# controle_motor_comunicacao.net
KiCad netlist of a schematic drawn in Altium Designer
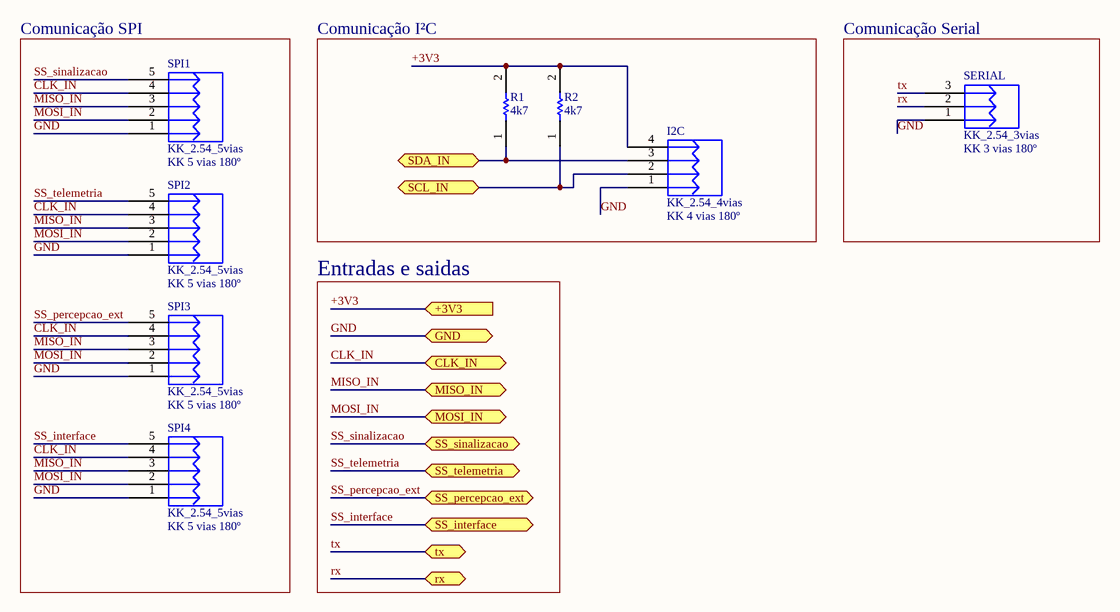
[diagram p0: controle_motor_comunicacao.SchDoc]

(export (version "E")
  (design (tool "Eeschema 10.0.6"))
  (components
    (comp (ref "I2C")
      (value "KK_2.54_4vias")
      (footprint "KK_4vias_180°")
      (description "Conector KK 2.54mm 4 vias")
      (fields (field (name "VALOR") "KK 4 vias 180º"))
      (libsource (lib "Conectores_Sch") (part "KK_2.54_4vias"))
    )
    (comp (ref "R1")
      (value "4k7")
      (footprint "RESC3216X60N")
      (description "RES 1206 5%")
      (fields
        (field (name "MANUFACTURER_PART_NUMBER") "CRCW12064K70FKEA")
        (field (name "MOUSER PART NUMBER") "71-CRCW1206-4.7K-E3")
      )
      (libsource (lib "RoboHospitalar") (part "RES 1206"))
    )
    (comp (ref "R2")
      (value "4k7")
      (footprint "RESC3216X60N")
      (description "RES 1206 5%")
      (fields
        (field (name "MANUFACTURER_PART_NUMBER") "CRCW12064K70FKEA")
        (field (name "MOUSER PART NUMBER") "71-CRCW1206-4.7K-E3")
      )
      (libsource (lib "RoboHospitalar") (part "RES 1206"))
    )
    (comp (ref "SERIAL")
      (value "KK_2.54_3vias")
      (footprint "KK_3vias_180º")
      (description "Conector KK 2.54mm 3 vias")
      (fields (field (name "VALOR") "KK 3 vias 180º"))
      (libsource (lib "Conectores_Sch") (part "KK_2.54_3vias"))
    )
    (comp (ref "SPI1")
      (value "KK_2.54_5vias")
      (footprint "KK_5vias_180°")
      (description "Conector KK 2.54mm 5 vias")
      (fields (field (name "VALOR") "KK 5 vias 180º"))
      (libsource (lib "Conectores_Sch") (part "KK_2.54_5vias"))
    )
    (comp (ref "SPI2")
      (value "KK_2.54_5vias")
      (footprint "KK_5vias_180°")
      (description "Conector KK 2.54mm 5 vias")
      (fields (field (name "VALOR") "KK 5 vias 180º"))
      (libsource (lib "Conectores_Sch") (part "KK_2.54_5vias"))
    )
    (comp (ref "SPI3")
      (value "KK_2.54_5vias")
      (footprint "KK_5vias_180°")
      (description "Conector KK 2.54mm 5 vias")
      (fields (field (name "VALOR") "KK 5 vias 180º"))
      (libsource (lib "Conectores_Sch") (part "KK_2.54_5vias"))
    )
    (comp (ref "SPI4")
      (value "KK_2.54_5vias")
      (footprint "KK_5vias_180°")
      (description "Conector KK 2.54mm 5 vias")
      (fields (field (name "VALOR") "KK 5 vias 180º"))
      (libsource (lib "Conectores_Sch") (part "KK_2.54_5vias"))
    )
  )
  (nets
    (net (code "1") (name "/+3V3") (class "Default")
      (node (ref "I2C") (pin "4") (pintype "passive"))
      (node (ref "R1") (pin "2") (pinfunction "2_2") (pintype "passive"))
      (node (ref "R2") (pin "2") (pinfunction "2_2") (pintype "passive"))
    )
    (net (code "2") (name "/CLK_IN") (class "Default")
      (node (ref "SPI1") (pin "4") (pintype "passive"))
      (node (ref "SPI2") (pin "4") (pintype "passive"))
      (node (ref "SPI3") (pin "4") (pintype "passive"))
      (node (ref "SPI4") (pin "4") (pintype "passive"))
    )
    (net (code "3") (name "/GND") (class "Default")
      (node (ref "I2C") (pin "1") (pintype "passive"))
      (node (ref "SERIAL") (pin "1") (pintype "passive"))
      (node (ref "SPI1") (pin "1") (pintype "passive"))
      (node (ref "SPI2") (pin "1") (pintype "passive"))
      (node (ref "SPI3") (pin "1") (pintype "passive"))
      (node (ref "SPI4") (pin "1") (pintype "passive"))
    )
    (net (code "4") (name "/MISO_IN") (class "Default")
      (node (ref "SPI1") (pin "3") (pintype "passive"))
      (node (ref "SPI2") (pin "3") (pintype "passive"))
      (node (ref "SPI3") (pin "3") (pintype "passive"))
      (node (ref "SPI4") (pin "3") (pintype "passive"))
    )
    (net (code "5") (name "/MOSI_IN") (class "Default")
      (node (ref "SPI1") (pin "2") (pintype "passive"))
      (node (ref "SPI2") (pin "2") (pintype "passive"))
      (node (ref "SPI3") (pin "2") (pintype "passive"))
      (node (ref "SPI4") (pin "2") (pintype "passive"))
    )
    (net (code "6") (name "/SCL_IN") (class "Default")
      (node (ref "I2C") (pin "2") (pintype "passive"))
      (node (ref "R2") (pin "1") (pinfunction "1_1") (pintype "passive"))
    )
    (net (code "7") (name "/SDA_IN") (class "Default")
      (node (ref "I2C") (pin "3") (pintype "passive"))
      (node (ref "R1") (pin "1") (pinfunction "1_1") (pintype "passive"))
    )
    (net (code "8") (name "/SS_interface") (class "Default")
      (node (ref "SPI4") (pin "5") (pintype "passive"))
    )
    (net (code "9") (name "/SS_percepcao_ext") (class "Default")
      (node (ref "SPI3") (pin "5") (pintype "passive"))
    )
    (net (code "10") (name "/SS_sinalizacao") (class "Default")
      (node (ref "SPI1") (pin "5") (pintype "passive"))
    )
    (net (code "11") (name "/SS_telemetria") (class "Default")
      (node (ref "SPI2") (pin "5") (pintype "passive"))
    )
    (net (code "12") (name "/rx") (class "Default") (node (ref "SERIAL") (pin "2") (pintype "passive")))
    (net (code "13") (name "/tx") (class "Default") (node (ref "SERIAL") (pin "3") (pintype "passive")))
  )
)
